# 13_FLOW_Sensor.net
KiCad netlist of a schematic drawn in Altium Designer
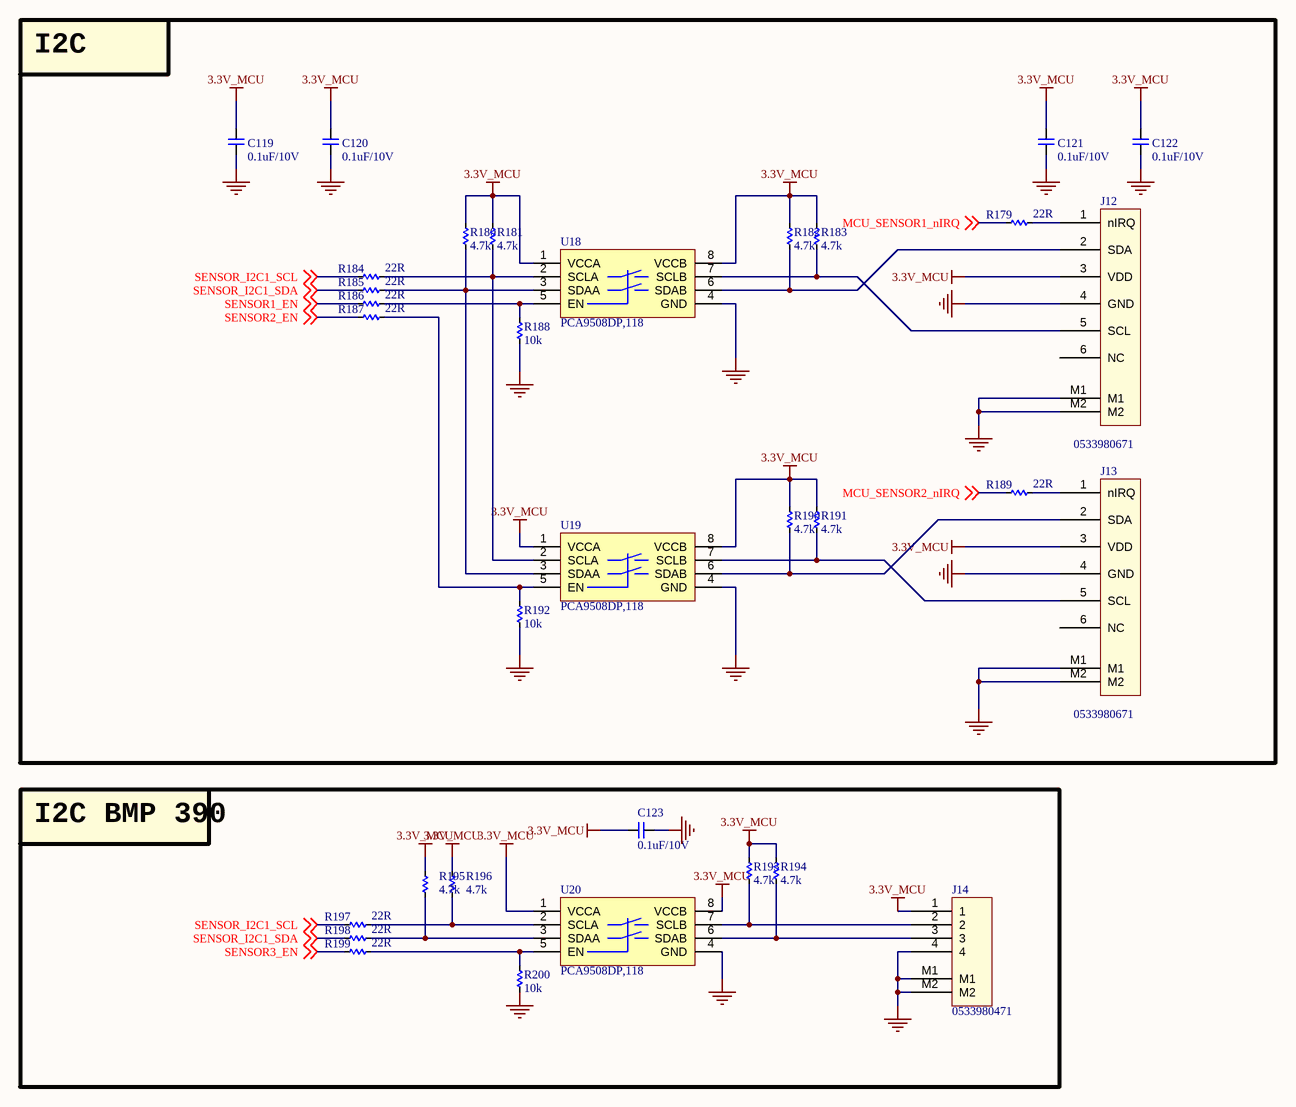
[diagram p0: 13_FLOW_Sensor.SchDoc]

(export (version "E")
  (design (tool "Eeschema 10.0.6"))
  (components
    (comp (ref "C119")
      (value "0.1uF/10V")
      (footprint "CAP_C_1005X60")
      (description "CAP CHIP")
      (libsource (lib "LABLIB") (part "_CAP_C_2"))
    )
    (comp (ref "C120")
      (value "0.1uF/10V")
      (footprint "CAP_C_1005X60")
      (description "CAP CHIP")
      (libsource (lib "LABLIB") (part "_CAP_C_2"))
    )
    (comp (ref "C121")
      (value "0.1uF/10V")
      (footprint "CAP_C_1005X60")
      (description "CAP CHIP")
      (libsource (lib "LABLIB") (part "_CAP_C_2"))
    )
    (comp (ref "C122")
      (value "0.1uF/10V")
      (footprint "CAP_C_1005X60")
      (description "CAP CHIP")
      (libsource (lib "LABLIB") (part "_CAP_C_2"))
    )
    (comp (ref "C123")
      (value "0.1uF/10V")
      (footprint "CAP_C_1005X60")
      (description "CAP CHIP")
      (libsource (lib "LABLIB") (part "_CAP_C_2"))
    )
    (comp (ref "J12")
      (value "0533980671")
      (footprint "MOLEX_0533980671")
      (libsource (lib "new_component") (part "FLOW_SENSOR"))
    )
    (comp (ref "J13")
      (value "0533980671")
      (footprint "MOLEX_0533980671")
      (libsource (lib "new_component") (part "FLOW_SENSOR"))
    )
    (comp (ref "J14")
      (value "0533980471")
      (footprint "MOLEX_0533980471")
      (libsource (lib "LABLIB") (part "Header 4x1_2M"))
    )
    (comp (ref "R179")
      (value "22R")
      (footprint "RES_C_1005X40")
      (description "RES")
      (libsource (lib "LABLIB") (part "_RES_B_2"))
    )
    (comp (ref "R180")
      (value "4.7k")
      (footprint "RES_C_1005X40")
      (description "RES")
      (libsource (lib "LABLIB") (part "_RES_B_2"))
    )
    (comp (ref "R181")
      (value "4.7k")
      (footprint "RES_C_1005X40")
      (description "RES")
      (libsource (lib "LABLIB") (part "_RES_B_2"))
    )
    (comp (ref "R182")
      (value "4.7k")
      (footprint "RES_C_1005X40")
      (description "RES")
      (libsource (lib "LABLIB") (part "_RES_B_2"))
    )
    (comp (ref "R183")
      (value "4.7k")
      (footprint "RES_C_1005X40")
      (description "RES")
      (libsource (lib "LABLIB") (part "_RES_B_2"))
    )
    (comp (ref "R184")
      (value "22R")
      (footprint "RES_C_1005X40")
      (description "RES")
      (libsource (lib "LABLIB") (part "_RES_B_2"))
    )
    (comp (ref "R185")
      (value "22R")
      (footprint "RES_C_1005X40")
      (description "RES")
      (libsource (lib "LABLIB") (part "_RES_B_2"))
    )
    (comp (ref "R186")
      (value "22R")
      (footprint "RES_C_1005X40")
      (description "RES")
      (libsource (lib "LABLIB") (part "_RES_B_2"))
    )
    (comp (ref "R187")
      (value "22R")
      (footprint "RES_C_1005X40")
      (description "RES")
      (libsource (lib "LABLIB") (part "_RES_B_2"))
    )
    (comp (ref "R188")
      (value "10k")
      (footprint "RES_C_1005X40")
      (description "RES")
      (libsource (lib "LABLIB") (part "_RES_B_2"))
    )
    (comp (ref "R189")
      (value "22R")
      (footprint "RES_C_1005X40")
      (description "RES")
      (libsource (lib "LABLIB") (part "_RES_B_2"))
    )
    (comp (ref "R190")
      (value "4.7k")
      (footprint "RES_C_1005X40")
      (description "RES")
      (libsource (lib "LABLIB") (part "_RES_B_2"))
    )
    (comp (ref "R191")
      (value "4.7k")
      (footprint "RES_C_1005X40")
      (description "RES")
      (libsource (lib "LABLIB") (part "_RES_B_2"))
    )
    (comp (ref "R192")
      (value "10k")
      (footprint "RES_C_1005X40")
      (description "RES")
      (libsource (lib "LABLIB") (part "_RES_B_2"))
    )
    (comp (ref "R193")
      (value "4.7k")
      (footprint "RES_C_1005X40")
      (description "RES")
      (libsource (lib "LABLIB") (part "_RES_B_2"))
    )
    (comp (ref "R194")
      (value "4.7k")
      (footprint "RES_C_1005X40")
      (description "RES")
      (libsource (lib "LABLIB") (part "_RES_B_2"))
    )
    (comp (ref "R195")
      (value "4.7k")
      (footprint "RES_C_1005X40")
      (description "RES")
      (libsource (lib "LABLIB") (part "_RES_B_2"))
    )
    (comp (ref "R196")
      (value "4.7k")
      (footprint "RES_C_1005X40")
      (description "RES")
      (libsource (lib "LABLIB") (part "_RES_B_2"))
    )
    (comp (ref "R197")
      (value "22R")
      (footprint "RES_C_1005X40")
      (description "RES")
      (libsource (lib "LABLIB") (part "_RES_B_2"))
    )
    (comp (ref "R198")
      (value "22R")
      (footprint "RES_C_1005X40")
      (description "RES")
      (libsource (lib "LABLIB") (part "_RES_B_2"))
    )
    (comp (ref "R199")
      (value "22R")
      (footprint "RES_C_1005X40")
      (description "RES")
      (libsource (lib "LABLIB") (part "_RES_B_2"))
    )
    (comp (ref "R200")
      (value "10k")
      (footprint "RES_C_1005X40")
      (description "RES")
      (libsource (lib "LABLIB") (part "_RES_B_2"))
    )
    (comp (ref "U18")
      (value "PCA9508DP,118")
      (footprint "TSOP8")
      (libsource (lib "EXP_HW_V3") (part "PCA9508DP,118"))
    )
    (comp (ref "U19")
      (value "PCA9508DP,118")
      (footprint "TSOP8")
      (libsource (lib "EXP_HW_V3") (part "PCA9508DP,118"))
    )
    (comp (ref "U20")
      (value "PCA9508DP,118")
      (footprint "TSOP8")
      (libsource (lib "EXP_HW_V3") (part "PCA9508DP,118"))
    )
  )
  (nets
    (net (code "1") (name "3.3V_MCU") (class "Default")
      (node (ref "C119") (pin "2") (pinfunction "2_2") (pintype "passive"))
      (node (ref "C120") (pin "2") (pinfunction "2_2") (pintype "passive"))
      (node (ref "C121") (pin "2") (pinfunction "2_2") (pintype "passive"))
      (node (ref "C122") (pin "2") (pinfunction "2_2") (pintype "passive"))
      (node (ref "C123") (pin "2") (pinfunction "2_2") (pintype "passive"))
      (node (ref "J12") (pin "3") (pinfunction "VDD_3") (pintype "passive"))
      (node (ref "J13") (pin "3") (pinfunction "VDD_3") (pintype "passive"))
      (node (ref "J14") (pin "1") (pinfunction "1_1") (pintype "passive"))
      (node (ref "R180") (pin "1") (pinfunction "1_1") (pintype "passive"))
      (node (ref "R181") (pin "1") (pinfunction "1_1") (pintype "passive"))
      (node (ref "R182") (pin "1") (pinfunction "1_1") (pintype "passive"))
      (node (ref "R183") (pin "1") (pinfunction "1_1") (pintype "passive"))
      (node (ref "R190") (pin "1") (pinfunction "1_1") (pintype "passive"))
      (node (ref "R191") (pin "1") (pinfunction "1_1") (pintype "passive"))
      (node (ref "R193") (pin "1") (pinfunction "1_1") (pintype "passive"))
      (node (ref "R194") (pin "1") (pinfunction "1_1") (pintype "passive"))
      (node (ref "R195") (pin "1") (pinfunction "1_1") (pintype "passive"))
      (node (ref "R196") (pin "1") (pinfunction "1_1") (pintype "passive"))
      (node (ref "U18") (pin "1") (pinfunction "VCCA_1") (pintype "passive"))
      (node (ref "U18") (pin "8") (pinfunction "VCCB_8") (pintype "passive"))
      (node (ref "U19") (pin "1") (pinfunction "VCCA_1") (pintype "passive"))
      (node (ref "U19") (pin "8") (pinfunction "VCCB_8") (pintype "passive"))
      (node (ref "U20") (pin "1") (pinfunction "VCCA_1") (pintype "passive"))
      (node (ref "U20") (pin "8") (pinfunction "VCCB_8") (pintype "passive"))
    )
    (net (code "2") (name "GND") (class "Default")
      (node (ref "C119") (pin "1") (pinfunction "1_1") (pintype "passive"))
      (node (ref "C120") (pin "1") (pinfunction "1_1") (pintype "passive"))
      (node (ref "C121") (pin "1") (pinfunction "1_1") (pintype "passive"))
      (node (ref "C122") (pin "1") (pinfunction "1_1") (pintype "passive"))
      (node (ref "C123") (pin "1") (pinfunction "1_1") (pintype "passive"))
      (node (ref "J12") (pin "4") (pinfunction "GND_4") (pintype "passive"))
      (node (ref "J12") (pin "M1") (pinfunction "M1_M1") (pintype "passive"))
      (node (ref "J12") (pin "M2") (pinfunction "M2_M2") (pintype "passive"))
      (node (ref "J13") (pin "4") (pinfunction "GND_4") (pintype "passive"))
      (node (ref "J13") (pin "M1") (pinfunction "M1_M1") (pintype "passive"))
      (node (ref "J13") (pin "M2") (pinfunction "M2_M2") (pintype "passive"))
      (node (ref "J14") (pin "4") (pinfunction "4_4") (pintype "passive"))
      (node (ref "J14") (pin "M1") (pinfunction "M1_M1") (pintype "passive"))
      (node (ref "J14") (pin "M2") (pinfunction "M2_M2") (pintype "passive"))
      (node (ref "R188") (pin "2") (pinfunction "2_2") (pintype "passive"))
      (node (ref "R192") (pin "2") (pinfunction "2_2") (pintype "passive"))
      (node (ref "R200") (pin "2") (pinfunction "2_2") (pintype "passive"))
      (node (ref "U18") (pin "4") (pinfunction "GND_4") (pintype "passive"))
      (node (ref "U19") (pin "4") (pinfunction "GND_4") (pintype "passive"))
      (node (ref "U20") (pin "4") (pinfunction "GND_4") (pintype "passive"))
    )
    (net (code "3") (name "MCU_SENSOR1_nIRQ") (class "Default")
      (node (ref "R179") (pin "2") (pinfunction "2_2") (pintype "passive"))
    )
    (net (code "4") (name "MCU_SENSOR2_nIRQ") (class "Default")
      (node (ref "R189") (pin "2") (pinfunction "2_2") (pintype "passive"))
    )
    (net (code "5") (name "Net-(J12-SCL)") (class "Default")
      (node (ref "J12") (pin "5") (pinfunction "SCL_5") (pintype "passive"))
      (node (ref "R183") (pin "2") (pinfunction "2_2") (pintype "passive"))
      (node (ref "U18") (pin "7") (pinfunction "SCLB_7") (pintype "passive"))
    )
    (net (code "6") (name "Net-(J12-SDA)") (class "Default")
      (node (ref "J12") (pin "2") (pinfunction "SDA_2") (pintype "passive"))
      (node (ref "R182") (pin "2") (pinfunction "2_2") (pintype "passive"))
      (node (ref "U18") (pin "6") (pinfunction "SDAB_6") (pintype "passive"))
    )
    (net (code "7") (name "Net-(J12-nIRQ)") (class "Default")
      (node (ref "J12") (pin "1") (pinfunction "nIRQ_1") (pintype "passive"))
      (node (ref "R179") (pin "1") (pinfunction "1_1") (pintype "passive"))
    )
    (net (code "8") (name "Net-(J13-SCL)") (class "Default")
      (node (ref "J13") (pin "5") (pinfunction "SCL_5") (pintype "passive"))
      (node (ref "R191") (pin "2") (pinfunction "2_2") (pintype "passive"))
      (node (ref "U19") (pin "7") (pinfunction "SCLB_7") (pintype "passive"))
    )
    (net (code "9") (name "Net-(J13-SDA)") (class "Default")
      (node (ref "J13") (pin "2") (pinfunction "SDA_2") (pintype "passive"))
      (node (ref "R190") (pin "2") (pinfunction "2_2") (pintype "passive"))
      (node (ref "U19") (pin "6") (pinfunction "SDAB_6") (pintype "passive"))
    )
    (net (code "10") (name "Net-(J13-nIRQ)") (class "Default")
      (node (ref "J13") (pin "1") (pinfunction "nIRQ_1") (pintype "passive"))
      (node (ref "R189") (pin "1") (pinfunction "1_1") (pintype "passive"))
    )
    (net (code "11") (name "Net-(U18-EN)") (class "Default")
      (node (ref "R186") (pin "1") (pinfunction "1_1") (pintype "passive"))
      (node (ref "R188") (pin "1") (pinfunction "1_1") (pintype "passive"))
      (node (ref "U18") (pin "5") (pinfunction "EN_5") (pintype "passive"))
    )
    (net (code "12") (name "Net-(U18-SCLA)") (class "Default")
      (node (ref "R181") (pin "2") (pinfunction "2_2") (pintype "passive"))
      (node (ref "R184") (pin "1") (pinfunction "1_1") (pintype "passive"))
      (node (ref "U18") (pin "2") (pinfunction "SCLA_2") (pintype "passive"))
      (node (ref "U19") (pin "2") (pinfunction "SCLA_2") (pintype "passive"))
    )
    (net (code "13") (name "Net-(U18-SDAA)") (class "Default")
      (node (ref "R180") (pin "2") (pinfunction "2_2") (pintype "passive"))
      (node (ref "R185") (pin "1") (pinfunction "1_1") (pintype "passive"))
      (node (ref "U18") (pin "3") (pinfunction "SDAA_3") (pintype "passive"))
      (node (ref "U19") (pin "3") (pinfunction "SDAA_3") (pintype "passive"))
    )
    (net (code "14") (name "Net-(U19-EN)") (class "Default")
      (node (ref "R187") (pin "1") (pinfunction "1_1") (pintype "passive"))
      (node (ref "R192") (pin "1") (pinfunction "1_1") (pintype "passive"))
      (node (ref "U19") (pin "5") (pinfunction "EN_5") (pintype "passive"))
    )
    (net (code "15") (name "Net-(U20-EN)") (class "Default")
      (node (ref "R199") (pin "1") (pinfunction "1_1") (pintype "passive"))
      (node (ref "R200") (pin "1") (pinfunction "1_1") (pintype "passive"))
      (node (ref "U20") (pin "5") (pinfunction "EN_5") (pintype "passive"))
    )
    (net (code "16") (name "Net-(U20-SCLA)") (class "Default")
      (node (ref "R196") (pin "2") (pinfunction "2_2") (pintype "passive"))
      (node (ref "R197") (pin "1") (pinfunction "1_1") (pintype "passive"))
      (node (ref "U20") (pin "2") (pinfunction "SCLA_2") (pintype "passive"))
    )
    (net (code "17") (name "Net-(U20-SCLB)") (class "Default")
      (node (ref "J14") (pin "2") (pinfunction "2_2") (pintype "passive"))
      (node (ref "R193") (pin "2") (pinfunction "2_2") (pintype "passive"))
      (node (ref "U20") (pin "7") (pinfunction "SCLB_7") (pintype "passive"))
    )
    (net (code "18") (name "Net-(U20-SDAA)") (class "Default")
      (node (ref "R195") (pin "2") (pinfunction "2_2") (pintype "passive"))
      (node (ref "R198") (pin "1") (pinfunction "1_1") (pintype "passive"))
      (node (ref "U20") (pin "3") (pinfunction "SDAA_3") (pintype "passive"))
    )
    (net (code "19") (name "Net-(U20-SDAB)") (class "Default")
      (node (ref "J14") (pin "3") (pinfunction "3_3") (pintype "passive"))
      (node (ref "R194") (pin "2") (pinfunction "2_2") (pintype "passive"))
      (node (ref "U20") (pin "6") (pinfunction "SDAB_6") (pintype "passive"))
    )
    (net (code "20") (name "SENSOR1_EN") (class "Default")
      (node (ref "R186") (pin "2") (pinfunction "2_2") (pintype "passive"))
    )
    (net (code "21") (name "SENSOR2_EN") (class "Default")
      (node (ref "R187") (pin "2") (pinfunction "2_2") (pintype "passive"))
    )
    (net (code "22") (name "SENSOR3_EN") (class "Default")
      (node (ref "R199") (pin "2") (pinfunction "2_2") (pintype "passive"))
    )
    (net (code "23") (name "SENSOR_I2C1_SCL") (class "Default")
      (node (ref "R184") (pin "2") (pinfunction "2_2") (pintype "passive"))
      (node (ref "R197") (pin "2") (pinfunction "2_2") (pintype "passive"))
    )
    (net (code "24") (name "SENSOR_I2C1_SDA") (class "Default")
      (node (ref "R185") (pin "2") (pinfunction "2_2") (pintype "passive"))
      (node (ref "R198") (pin "2") (pinfunction "2_2") (pintype "passive"))
    )
    (net (code "25") (name "unconnected-(J12-NC-Pad6)") (class "Default")
      (node (ref "J12") (pin "6") (pinfunction "NC_6") (pintype "passive"))
    )
    (net (code "26") (name "unconnected-(J13-NC-Pad6)") (class "Default")
      (node (ref "J13") (pin "6") (pinfunction "NC_6") (pintype "passive"))
    )
  )
)
